# Alim_Ticketing_Slave.net
KiCad netlist of a schematic drawn in Altium Designer
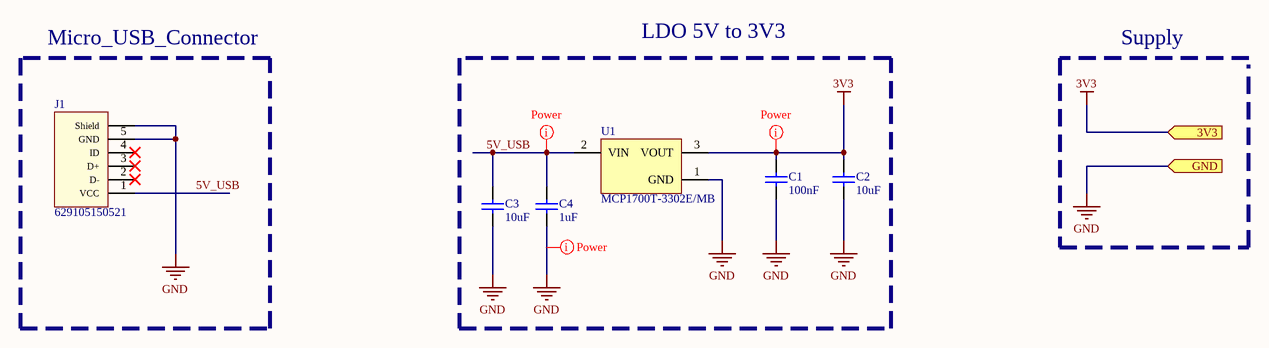
[diagram p0: Alim_Ticketing_Slave.SchDoc]

(export (version "E")
  (design (tool "Eeschema 10.0.6"))
  (components
    (comp (ref "C1")
      (value "100nF")
      (footprint "6-0805_N")
      (description "CAP 100nF 16V ±10% 0805 (2012 Metric) Thickness 1.45mm SMD")
      (fields (field (name "TOLERANCE") "Â±10%"))
      (libsource (lib "Altium Content Vault") (part "CAP"))
    )
    (comp (ref "C2")
      (value "10uF")
      (footprint "6-0805_N")
      (description "CAP 10uF 16V ±20% 0805 (2012 Metric) Thickness 1mm SMD")
      (fields (field (name "TOLERANCE") "Â±20%"))
      (libsource (lib "Altium Content Vault") (part "CAP"))
    )
    (comp (ref "C3")
      (value "10uF")
      (footprint "6-0805_N")
      (description "CAP 10uF 16V ±20% 0805 (2012 Metric) Thickness 1mm SMD")
      (fields (field (name "TOLERANCE") "Â±20%"))
      (libsource (lib "Altium Content Vault") (part "CAP"))
    )
    (comp (ref "C4")
      (value "1uF")
      (footprint "6-0805_N")
      (description "CAP 10uF 16V ±20% 0805 (2012 Metric) Thickness 1mm SMD")
      (fields (field (name "TOLERANCE") "Â±20%"))
      (libsource (lib "Altium Content Vault") (part "CAP"))
    )
    (comp (ref "J1")
      (value "629105150521")
      (footprint "629105150521")
      (description "Micro USB 2.0 SMT Type B Horizontal 5 Contacts High Current WR-COM")
      (fields (field (name "PUBLISHER") "Wurth Elektronik"))
      (libsource (lib "ALTIUM-WR-COM-rev18a") (part "629105150521"))
    )
    (comp (ref "U1")
      (value "MCP1700T-3302E/MB")
      (footprint "SOT-89-MB3_M")
      (description "Low Quiescent Current LDO, 3-Pin SOT-89, Extended Temperature, Tape and Reel")
      (libsource (lib "Altium Content Vault") (part "PM-LINEREG-MCP1700-IL3A"))
    )
  )
  (nets
    (net (code "1") (name "/5V_USB") (class "Default")
      (node (ref "C3") (pin "2") (pinfunction "2_2") (pintype "passive"))
      (node (ref "C4") (pin "2") (pinfunction "2_2") (pintype "passive"))
      (node (ref "J1") (pin "1") (pinfunction "VCC_1") (pintype "passive"))
      (node (ref "U1") (pin "2") (pinfunction "VIN_2") (pintype "power_in"))
    )
    (net (code "2") (name "3V3") (class "Default")
      (node (ref "C1") (pin "2") (pinfunction "2_2") (pintype "passive"))
      (node (ref "C2") (pin "2") (pinfunction "2_2") (pintype "passive"))
      (node (ref "U1") (pin "3") (pinfunction "VOUT_3") (pintype "power_in"))
    )
    (net (code "3") (name "GND") (class "Default")
      (node (ref "C1") (pin "1") (pinfunction "1_1") (pintype "passive"))
      (node (ref "C2") (pin "1") (pinfunction "1_1") (pintype "passive"))
      (node (ref "C3") (pin "1") (pinfunction "1_1") (pintype "passive"))
      (node (ref "C4") (pin "1") (pinfunction "1_1") (pintype "passive"))
      (node (ref "J1") (pin "5") (pinfunction "GND_5") (pintype "passive"))
      (node (ref "J1") (pin "Shell") (pinfunction "Shield_Shell") (pintype "passive"))
      (node (ref "U1") (pin "1") (pinfunction "GND_1") (pintype "power_in"))
    )
    (net (code "4") (name "unconnected-(J1-D+-Pad3)") (class "Default")
      (node (ref "J1") (pin "3") (pinfunction "D+_3") (pintype "passive+no_connect"))
    )
    (net (code "5") (name "unconnected-(J1-D--Pad2)") (class "Default")
      (node (ref "J1") (pin "2") (pinfunction "D-_2") (pintype "passive+no_connect"))
    )
    (net (code "6") (name "unconnected-(J1-ID-Pad4)") (class "Default")
      (node (ref "J1") (pin "4") (pinfunction "ID_4") (pintype "passive+no_connect"))
    )
  )
)
